# 6_Connector.net
KiCad netlist of a schematic drawn in Altium Designer
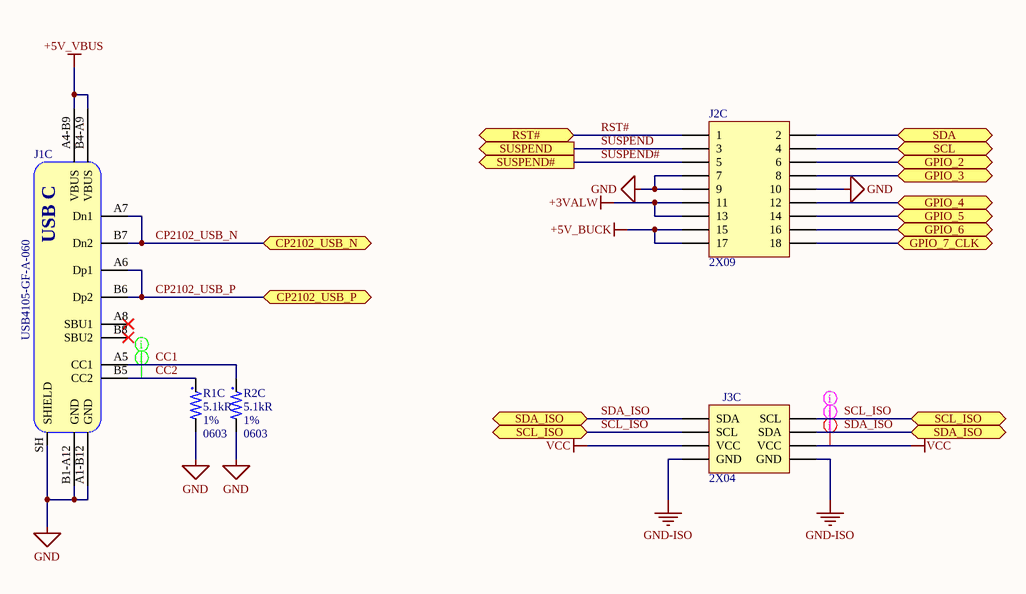
[diagram p0: 6_Connector.SchDoc]

(export (version "E")
  (design (tool "Eeschema 10.0.6"))
  (components
    (comp (ref "J1C")
      (value "USB4105-GF-A-060")
      (footprint "USB-Type-C-16-Pin-SMT")
      (description "USB Connector Type C SMT 16 Pin\r\n(Power pins joints = 12 pins)")
      (fields (field (name "MANUFACTURER") "GCT"))
      (libsource (lib "Lib_Connector") (part "USB-Type-C-16-Pin-SMT"))
    )
    (comp (ref "J2C")
      (value "2X09")
      (footprint "PinHeader_2x09_P2.54mm_Vertical")
      (libsource (lib "Lib_Connector_PinHeader_2.54mm") (part "PinHeader 2X09 DU"))
    )
    (comp (ref "J3C")
      (value "2X04")
      (footprint "PinHeader_2x04_P2.54mm_Vertical")
      (libsource (lib "Lib_Connector_PinHeader_2.54mm") (part "I2C_2X04_P2.54mm"))
    )
    (comp (ref "R1C")
      (value "5.1kR")
      (footprint "R0603-MFG")
      (description "SMD Chip Resistor, 5.1 kOhm, ± 1%, 100 mW, 0603 [1608 Metric], Thick Film, General Purpose")
      (fields
        (field (name "MANUFACTURER") "Vishay")
        (field (name "MANUFACTURER PART NUMBER") "CRCW06035K10FKEA")
        (field (name "TOLERANCE") "1%")
        (field (name "CASE/PACKAGE") "0603")
      )
      (libsource (lib "Lib_Register_0603") (part "5.1K"))
    )
    (comp (ref "R2C")
      (value "5.1kR")
      (footprint "R0603-MFG")
      (description "SMD Chip Resistor, 5.1 kOhm, ± 1%, 100 mW, 0603 [1608 Metric], Thick Film, General Purpose")
      (fields
        (field (name "MANUFACTURER") "Vishay")
        (field (name "MANUFACTURER PART NUMBER") "CRCW06035K10FKEA")
        (field (name "TOLERANCE") "1%")
        (field (name "CASE/PACKAGE") "0603")
      )
      (libsource (lib "Lib_Register_0603") (part "5.1K"))
    )
  )
  (nets
    (net (code "1") (name "+3VALW") (class "Default")
      (node (ref "J2C") (pin "11") (pinfunction "11_11") (pintype "passive"))
      (node (ref "J2C") (pin "13") (pinfunction "13_13") (pintype "passive"))
    )
    (net (code "2") (name "+5V_BUCK") (class "Default")
      (node (ref "J2C") (pin "15") (pinfunction "15_15") (pintype "passive"))
      (node (ref "J2C") (pin "17") (pinfunction "17_17") (pintype "passive"))
    )
    (net (code "3") (name "+5V_VBUS") (class "Default")
      (node (ref "J1C") (pin "A4-B9") (pinfunction "VBUS_A4-B9") (pintype "passive"))
      (node (ref "J1C") (pin "B4-A9") (pinfunction "VBUS_B4-A9") (pintype "passive"))
    )
    (net (code "4") (name "/CC1") (class "Default")
      (node (ref "J1C") (pin "A5") (pinfunction "CC1_A5") (pintype "passive"))
      (node (ref "R2C") (pin "1") (pinfunction "1_1") (pintype "passive"))
    )
    (net (code "5") (name "/CC2") (class "Default")
      (node (ref "J1C") (pin "B5") (pinfunction "CC2_B5") (pintype "passive"))
      (node (ref "R1C") (pin "1") (pinfunction "1_1") (pintype "passive"))
    )
    (net (code "6") (name "/CP2102_USB_N") (class "Default")
      (node (ref "J1C") (pin "A7") (pinfunction "Dn1_A7") (pintype "passive"))
      (node (ref "J1C") (pin "B7") (pinfunction "Dn2_B7") (pintype "passive"))
    )
    (net (code "7") (name "/CP2102_USB_P") (class "Default")
      (node (ref "J1C") (pin "A6") (pinfunction "Dp1_A6") (pintype "passive"))
      (node (ref "J1C") (pin "B6") (pinfunction "Dp2_B6") (pintype "passive"))
    )
    (net (code "8") (name "/GPIO_2") (class "Default")
      (node (ref "J2C") (pin "6") (pinfunction "6_6") (pintype "passive"))
    )
    (net (code "9") (name "/GPIO_3") (class "Default")
      (node (ref "J2C") (pin "8") (pinfunction "8_8") (pintype "passive"))
    )
    (net (code "10") (name "/GPIO_4") (class "Default")
      (node (ref "J2C") (pin "12") (pinfunction "12_12") (pintype "passive"))
    )
    (net (code "11") (name "/GPIO_5") (class "Default")
      (node (ref "J2C") (pin "14") (pinfunction "14_14") (pintype "passive"))
    )
    (net (code "12") (name "/GPIO_6") (class "Default")
      (node (ref "J2C") (pin "16") (pinfunction "16_16") (pintype "passive"))
    )
    (net (code "13") (name "/GPIO_7_CLK") (class "Default")
      (node (ref "J2C") (pin "18") (pinfunction "18_18") (pintype "passive"))
    )
    (net (code "14") (name "/RST#") (class "Default")
      (node (ref "J2C") (pin "1") (pinfunction "1_1") (pintype "passive"))
    )
    (net (code "15") (name "/SCL") (class "Default")
      (node (ref "J2C") (pin "4") (pinfunction "4_4") (pintype "passive"))
    )
    (net (code "16") (name "/SCL_ISO") (class "Default")
      (node (ref "J3C") (pin "6") (pinfunction "SCL_6") (pintype "passive"))
      (node (ref "J3C") (pin "7") (pinfunction "SCL_7") (pintype "passive"))
    )
    (net (code "17") (name "/SDA") (class "Default")
      (node (ref "J2C") (pin "2") (pinfunction "2_2") (pintype "passive"))
    )
    (net (code "18") (name "/SDA_ISO") (class "Default")
      (node (ref "J3C") (pin "5") (pinfunction "SDA_5") (pintype "passive"))
      (node (ref "J3C") (pin "8") (pinfunction "SDA_8") (pintype "passive"))
    )
    (net (code "19") (name "/SUSPEND") (class "Default")
      (node (ref "J2C") (pin "3") (pinfunction "3_3") (pintype "passive"))
    )
    (net (code "20") (name "/SUSPEND#") (class "Default")
      (node (ref "J2C") (pin "5") (pinfunction "5_5") (pintype "passive"))
    )
    (net (code "21") (name "GND") (class "Default")
      (node (ref "J1C") (pin "A1-B12") (pinfunction "GND_A1-B12") (pintype "passive"))
      (node (ref "J1C") (pin "B1-A12") (pinfunction "GND_B1-A12") (pintype "passive"))
      (node (ref "J1C") (pin "SH") (pinfunction "SHIELD_SH") (pintype "passive"))
      (node (ref "J2C") (pin "10") (pinfunction "10_10") (pintype "passive"))
      (node (ref "J2C") (pin "7") (pinfunction "7_7") (pintype "passive"))
      (node (ref "J2C") (pin "9") (pinfunction "9_9") (pintype "passive"))
      (node (ref "R1C") (pin "2") (pinfunction "2_2") (pintype "passive"))
      (node (ref "R2C") (pin "2") (pinfunction "2_2") (pintype "passive"))
    )
    (net (code "22") (name "GND-ISO") (class "Default")
      (node (ref "J3C") (pin "1") (pinfunction "GND_1") (pintype "passive"))
      (node (ref "J3C") (pin "2") (pinfunction "GND_2") (pintype "passive"))
    )
    (net (code "23") (name "VCC") (class "Default")
      (node (ref "J3C") (pin "3") (pinfunction "VCC_3") (pintype "passive"))
      (node (ref "J3C") (pin "4") (pinfunction "VCC_4") (pintype "passive"))
    )
    (net (code "24") (name "unconnected-(J1C-SBU1-PadA8)") (class "Default")
      (node (ref "J1C") (pin "A8") (pinfunction "SBU1_A8") (pintype "passive+no_connect"))
    )
    (net (code "25") (name "unconnected-(J1C-SBU2-PadB8)") (class "Default")
      (node (ref "J1C") (pin "B8") (pinfunction "SBU2_B8") (pintype "passive+no_connect"))
    )
  )
)
